# Supply_Fusing.net
KiCad netlist of a schematic drawn in Altium Designer
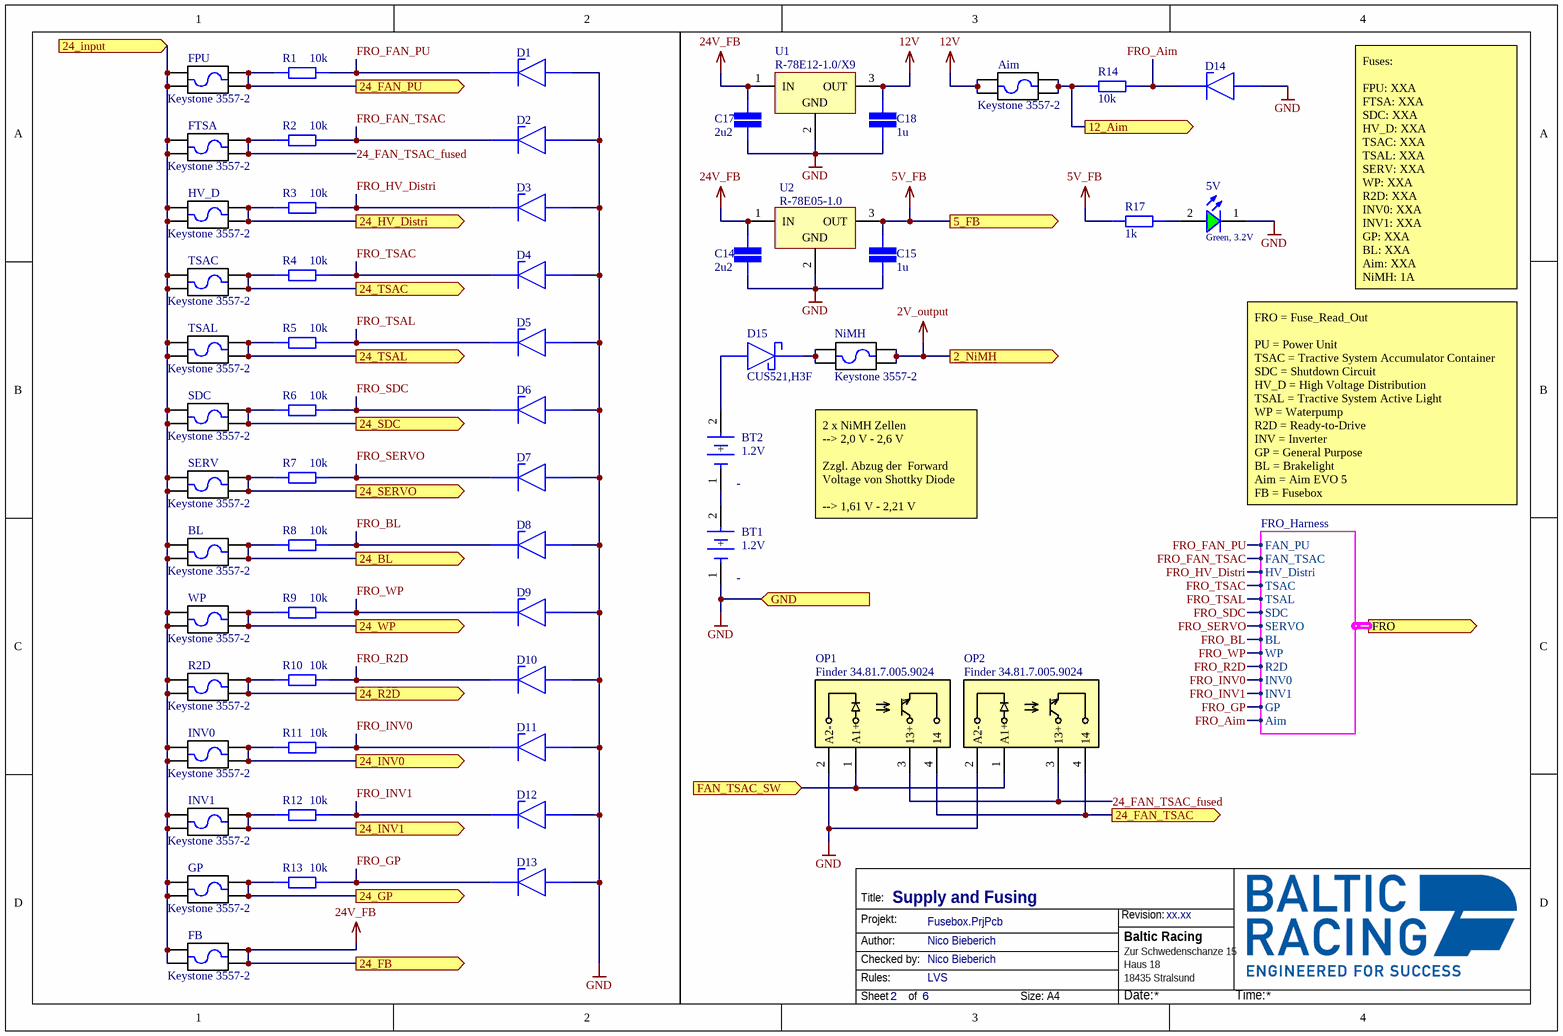
[diagram p0: Supply_Fusing.SchDoc]

(export (version "E")
  (design (tool "Eeschema 10.0.6"))
  (components
    (comp (ref "5V")
      (value "Green, 3.2V")
      (footprint "WL-SMCW_0603_H=0.7mm")
      (description "WL-SMCW SMT Mono-color Chip LED Waterclear, size 0603, Green, 3.2V, 140deg")
      (fields (field (name "PART NUMBER") "150060GS75000") (field (name "PUBLISHER") "Wurth Elektronik"))
      (libsource (lib "Altium_WL-SMCW (rev20a)") (part "150060GS75000"))
    )
    (comp (ref "Aim")
      (value "Keystone 3557-2")
      (footprint "Keystone 3557-2")
      (description "Keystone 3557-2\r\nFuse Holder")
      (libsource (lib "libNico") (part "Keystone 3557-2"))
    )
    (comp (ref "BL")
      (value "Keystone 3557-2")
      (footprint "Keystone 3557-2")
      (description "Keystone 3557-2\r\nFuse Holder")
      (libsource (lib "libNico") (part "Keystone 3557-2"))
    )
    (comp (ref "BT1")
      (value "Keystone 1020")
      (footprint "Keystone_1020_0")
      (description "BATT HOLDER BATTERY AAA SMD")
      (fields
        (field (name "PART NUMBER") "1020")
        (field (name "MANUFACTURER") "Keystone")
        (field (name "VOLTAGE") "1.2V")
      )
      (libsource (lib "libNico") (part "Keystone 1020"))
    )
    (comp (ref "BT2")
      (value "Keystone 1020")
      (footprint "Keystone_1020_0")
      (description "BATT HOLDER BATTERY AAA SMD")
      (fields
        (field (name "PART NUMBER") "1020")
        (field (name "MANUFACTURER") "Keystone")
        (field (name "VOLTAGE") "1.2V")
      )
      (libsource (lib "libNico") (part "Keystone 1020"))
    )
    (comp (ref "C14")
      (value "2u2")
      (footprint "CAP 0603/1608")
      (description "Capacitor with multiple Footprints")
      (fields (field (name "VOLTAGE") "50") (field (name "Comment") "SMD Capacitor"))
      (libsource (lib "Standardbauteile") (part "SMD Capacitor"))
    )
    (comp (ref "C15")
      (value "1u")
      (footprint "CAP 0603/1608")
      (description "Capacitor with multiple Footprints")
      (fields (field (name "VOLTAGE") "16") (field (name "Comment") "SMD Capacitor"))
      (libsource (lib "Standardbauteile") (part "SMD Capacitor"))
    )
    (comp (ref "C17")
      (value "2u2")
      (footprint "CAP 0603/1608")
      (description "Capacitor with multiple Footprints")
      (fields (field (name "VOLTAGE") "50") (field (name "Comment") "SMD Capacitor"))
      (libsource (lib "Standardbauteile") (part "SMD Capacitor"))
    )
    (comp (ref "C18")
      (value "1u")
      (footprint "CAP 0603/1608")
      (description "Capacitor with multiple Footprints")
      (fields (field (name "VOLTAGE") "16") (field (name "Comment") "SMD Capacitor"))
      (libsource (lib "Standardbauteile") (part "SMD Capacitor"))
    )
    (comp (ref "D1")
      (value "MM3Z4V7T1G")
      (footprint "SOD-323-2")
      (description "onsemi MM3Z4V7T1G\r\nZ-Diode, 4,7V")
      (libsource (lib "libNico") (part "MM3Z4V7T1G"))
    )
    (comp (ref "D2")
      (value "MM3Z4V7T1G")
      (footprint "SOD-323-2")
      (description "onsemi MM3Z4V7T1G\r\nZ-Diode, 4,7V")
      (libsource (lib "libNico") (part "MM3Z4V7T1G"))
    )
    (comp (ref "D3")
      (value "MM3Z4V7T1G")
      (footprint "SOD-323-2")
      (description "onsemi MM3Z4V7T1G\r\nZ-Diode, 4,7V")
      (libsource (lib "libNico") (part "MM3Z4V7T1G"))
    )
    (comp (ref "D4")
      (value "MM3Z4V7T1G")
      (footprint "SOD-323-2")
      (description "onsemi MM3Z4V7T1G\r\nZ-Diode, 4,7V")
      (libsource (lib "libNico") (part "MM3Z4V7T1G"))
    )
    (comp (ref "D5")
      (value "MM3Z4V7T1G")
      (footprint "SOD-323-2")
      (description "onsemi MM3Z4V7T1G\r\nZ-Diode, 4,7V")
      (libsource (lib "libNico") (part "MM3Z4V7T1G"))
    )
    (comp (ref "D6")
      (value "MM3Z4V7T1G")
      (footprint "SOD-323-2")
      (description "onsemi MM3Z4V7T1G\r\nZ-Diode, 4,7V")
      (libsource (lib "libNico") (part "MM3Z4V7T1G"))
    )
    (comp (ref "D7")
      (value "MM3Z4V7T1G")
      (footprint "SOD-323-2")
      (description "onsemi MM3Z4V7T1G\r\nZ-Diode, 4,7V")
      (libsource (lib "libNico") (part "MM3Z4V7T1G"))
    )
    (comp (ref "D8")
      (value "MM3Z4V7T1G")
      (footprint "SOD-323-2")
      (description "onsemi MM3Z4V7T1G\r\nZ-Diode, 4,7V")
      (libsource (lib "libNico") (part "MM3Z4V7T1G"))
    )
    (comp (ref "D9")
      (value "MM3Z4V7T1G")
      (footprint "SOD-323-2")
      (description "onsemi MM3Z4V7T1G\r\nZ-Diode, 4,7V")
      (libsource (lib "libNico") (part "MM3Z4V7T1G"))
    )
    (comp (ref "D10")
      (value "MM3Z4V7T1G")
      (footprint "SOD-323-2")
      (description "onsemi MM3Z4V7T1G\r\nZ-Diode, 4,7V")
      (libsource (lib "libNico") (part "MM3Z4V7T1G"))
    )
    (comp (ref "D11")
      (value "MM3Z4V7T1G")
      (footprint "SOD-323-2")
      (description "onsemi MM3Z4V7T1G\r\nZ-Diode, 4,7V")
      (libsource (lib "libNico") (part "MM3Z4V7T1G"))
    )
    (comp (ref "D12")
      (value "MM3Z4V7T1G")
      (footprint "SOD-323-2")
      (description "onsemi MM3Z4V7T1G\r\nZ-Diode, 4,7V")
      (libsource (lib "libNico") (part "MM3Z4V7T1G"))
    )
    (comp (ref "D13")
      (value "MM3Z4V7T1G")
      (footprint "SOD-323-2")
      (description "onsemi MM3Z4V7T1G\r\nZ-Diode, 4,7V")
      (libsource (lib "libNico") (part "MM3Z4V7T1G"))
    )
    (comp (ref "D14")
      (value "MM3Z4V7T1G")
      (footprint "SOD-323-2")
      (description "onsemi MM3Z4V7T1G\r\nZ-Diode, 4,7V")
      (libsource (lib "libNico") (part "MM3Z4V7T1G"))
    )
    (comp (ref "D15")
      (value "CUS521,H3F")
      (footprint "SOD-323-2")
      (description "Toshiba CUS521,H3F\r\nShottky-Diode\r\nForward: 390mV, Reverse: 30V")
      (libsource (lib "libNico") (part "CUS521,H3F"))
    )
    (comp (ref "FB")
      (value "Keystone 3557-2")
      (footprint "Keystone 3557-2")
      (description "Keystone 3557-2\r\nFuse Holder")
      (libsource (lib "libNico") (part "Keystone 3557-2"))
    )
    (comp (ref "FPU")
      (value "Keystone 3557-2")
      (footprint "Keystone 3557-2")
      (description "Keystone 3557-2\r\nFuse Holder")
      (libsource (lib "libNico") (part "Keystone 3557-2"))
    )
    (comp (ref "FTSA")
      (value "Keystone 3557-2")
      (footprint "Keystone 3557-2")
      (description "Keystone 3557-2\r\nFuse Holder")
      (libsource (lib "libNico") (part "Keystone 3557-2"))
    )
    (comp (ref "GP")
      (value "Keystone 3557-2")
      (footprint "Keystone 3557-2")
      (description "Keystone 3557-2\r\nFuse Holder")
      (libsource (lib "libNico") (part "Keystone 3557-2"))
    )
    (comp (ref "HV_D")
      (value "Keystone 3557-2")
      (footprint "Keystone 3557-2")
      (description "Keystone 3557-2\r\nFuse Holder")
      (libsource (lib "libNico") (part "Keystone 3557-2"))
    )
    (comp (ref "INV0")
      (value "Keystone 3557-2")
      (footprint "Keystone 3557-2")
      (description "Keystone 3557-2\r\nFuse Holder")
      (libsource (lib "libNico") (part "Keystone 3557-2"))
    )
    (comp (ref "INV1")
      (value "Keystone 3557-2")
      (footprint "Keystone 3557-2")
      (description "Keystone 3557-2\r\nFuse Holder")
      (libsource (lib "libNico") (part "Keystone 3557-2"))
    )
    (comp (ref "NiMH")
      (value "Keystone 3557-2")
      (footprint "Keystone 3557-2")
      (description "Keystone 3557-2\r\nFuse Holder")
      (libsource (lib "libNico") (part "Keystone 3557-2"))
    )
    (comp (ref "OP1")
      (value "Finder 34.81.7.005.9024")
      (footprint "Finder 34.81 Series")
      (description "Opto-Isolator\r\nFinder 34.81 series")
      (libsource (lib "libNico") (part "Finder 34.81 Series"))
    )
    (comp (ref "OP2")
      (value "Finder 34.81.7.005.9024")
      (footprint "Finder 34.81 Series")
      (description "Opto-Isolator\r\nFinder 34.81 series")
      (libsource (lib "libNico") (part "Finder 34.81 Series"))
    )
    (comp (ref "R1")
      (value "10k")
      (footprint "STACKPOLE CSR0603")
      (description "Resistor with multiple footprints")
      (fields (field (name "POWER") "0.1W") (field (name "Comment") "SMD Resistor"))
      (libsource (lib "Standardbauteile") (part "SMD Resistor"))
    )
    (comp (ref "R2")
      (value "10k")
      (footprint "STACKPOLE CSR0603")
      (description "Resistor with multiple footprints")
      (fields (field (name "POWER") "0.1W") (field (name "Comment") "SMD Resistor"))
      (libsource (lib "Standardbauteile") (part "SMD Resistor"))
    )
    (comp (ref "R2D")
      (value "Keystone 3557-2")
      (footprint "Keystone 3557-2")
      (description "Keystone 3557-2\r\nFuse Holder")
      (libsource (lib "libNico") (part "Keystone 3557-2"))
    )
    (comp (ref "R3")
      (value "10k")
      (footprint "STACKPOLE CSR0603")
      (description "Resistor with multiple footprints")
      (fields (field (name "POWER") "0.1W") (field (name "Comment") "SMD Resistor"))
      (libsource (lib "Standardbauteile") (part "SMD Resistor"))
    )
    (comp (ref "R4")
      (value "10k")
      (footprint "STACKPOLE CSR0603")
      (description "Resistor with multiple footprints")
      (fields (field (name "POWER") "0.1W") (field (name "Comment") "SMD Resistor"))
      (libsource (lib "Standardbauteile") (part "SMD Resistor"))
    )
    (comp (ref "R5")
      (value "10k")
      (footprint "STACKPOLE CSR0603")
      (description "Resistor with multiple footprints")
      (fields (field (name "POWER") "0.1W") (field (name "Comment") "SMD Resistor"))
      (libsource (lib "Standardbauteile") (part "SMD Resistor"))
    )
    (comp (ref "R6")
      (value "10k")
      (footprint "STACKPOLE CSR0603")
      (description "Resistor with multiple footprints")
      (fields (field (name "POWER") "0.1W") (field (name "Comment") "SMD Resistor"))
      (libsource (lib "Standardbauteile") (part "SMD Resistor"))
    )
    (comp (ref "R7")
      (value "10k")
      (footprint "STACKPOLE CSR0603")
      (description "Resistor with multiple footprints")
      (fields (field (name "POWER") "0.1W") (field (name "Comment") "SMD Resistor"))
      (libsource (lib "Standardbauteile") (part "SMD Resistor"))
    )
    (comp (ref "R8")
      (value "10k")
      (footprint "STACKPOLE CSR0603")
      (description "Resistor with multiple footprints")
      (fields (field (name "POWER") "0.1W") (field (name "Comment") "SMD Resistor"))
      (libsource (lib "Standardbauteile") (part "SMD Resistor"))
    )
    (comp (ref "R9")
      (value "10k")
      (footprint "STACKPOLE CSR0603")
      (description "Resistor with multiple footprints")
      (fields (field (name "POWER") "0.1W") (field (name "Comment") "SMD Resistor"))
      (libsource (lib "Standardbauteile") (part "SMD Resistor"))
    )
    (comp (ref "R10")
      (value "10k")
      (footprint "STACKPOLE CSR0603")
      (description "Resistor with multiple footprints")
      (fields (field (name "POWER") "0.1W") (field (name "Comment") "SMD Resistor"))
      (libsource (lib "Standardbauteile") (part "SMD Resistor"))
    )
    (comp (ref "R11")
      (value "10k")
      (footprint "STACKPOLE CSR0603")
      (description "Resistor with multiple footprints")
      (fields (field (name "POWER") "0.1W") (field (name "Comment") "SMD Resistor"))
      (libsource (lib "Standardbauteile") (part "SMD Resistor"))
    )
    (comp (ref "R12")
      (value "10k")
      (footprint "STACKPOLE CSR0603")
      (description "Resistor with multiple footprints")
      (fields (field (name "POWER") "0.1W") (field (name "Comment") "SMD Resistor"))
      (libsource (lib "Standardbauteile") (part "SMD Resistor"))
    )
    (comp (ref "R13")
      (value "10k")
      (footprint "STACKPOLE CSR0603")
      (description "Resistor with multiple footprints")
      (fields (field (name "POWER") "0.1W") (field (name "Comment") "SMD Resistor"))
      (libsource (lib "Standardbauteile") (part "SMD Resistor"))
    )
    (comp (ref "R14")
      (value "10k")
      (footprint "STACKPOLE CSR0603")
      (description "Resistor with multiple footprints")
      (fields (field (name "POWER") "0.1W") (field (name "Comment") "SMD Resistor"))
      (libsource (lib "Standardbauteile") (part "SMD Resistor"))
    )
    (comp (ref "R17")
      (value "1k")
      (footprint "STACKPOLE CSR0603")
      (description "Resistor with multiple footprints")
      (fields (field (name "POWER") "0.1W") (field (name "Comment") "SMD Resistor"))
      (libsource (lib "Standardbauteile") (part "SMD Resistor"))
    )
    (comp (ref "SDC")
      (value "Keystone 3557-2")
      (footprint "Keystone 3557-2")
      (description "Keystone 3557-2\r\nFuse Holder")
      (libsource (lib "libNico") (part "Keystone 3557-2"))
    )
    (comp (ref "SERV")
      (value "Keystone 3557-2")
      (footprint "Keystone 3557-2")
      (description "Keystone 3557-2\r\nFuse Holder")
      (libsource (lib "libNico") (part "Keystone 3557-2"))
    )
    (comp (ref "TSAC")
      (value "Keystone 3557-2")
      (footprint "Keystone 3557-2")
      (description "Keystone 3557-2\r\nFuse Holder")
      (libsource (lib "libNico") (part "Keystone 3557-2"))
    )
    (comp (ref "TSAL")
      (value "Keystone 3557-2")
      (footprint "Keystone 3557-2")
      (description "Keystone 3557-2\r\nFuse Holder")
      (libsource (lib "libNico") (part "Keystone 3557-2"))
    )
    (comp (ref "U1")
      (value "R-78E12-1.0/X9")
      (footprint "SIP3_RECOM")
      (description "Nonisolated 5V Switchmode converter")
      (libsource (lib "Standardbauteile") (part "R-78E05-1.0"))
    )
    (comp (ref "U2")
      (value "R-78E05-1.0")
      (footprint "SIP3_RECOM")
      (description "Nonisolated 5V Switchmode converter")
      (libsource (lib "Standardbauteile") (part "R-78E05-1.0"))
    )
    (comp (ref "WP")
      (value "Keystone 3557-2")
      (footprint "Keystone 3557-2")
      (description "Keystone 3557-2\r\nFuse Holder")
      (libsource (lib "libNico") (part "Keystone 3557-2"))
    )
  )
  (nets
    (net (code "2") (name "/12_Aim") (class "Default")
      (node (ref "Aim") (pin "O1") (pinfunction "O1_O1") (pintype "passive"))
      (node (ref "Aim") (pin "O2") (pinfunction "O2_O2") (pintype "passive"))
      (node (ref "R14") (pin "2") (pinfunction "2_2") (pintype "passive"))
    )
    (net (code "3") (name "/24_BL") (class "Default")
      (node (ref "BL") (pin "O1") (pinfunction "O1_O1") (pintype "passive"))
      (node (ref "BL") (pin "O2") (pinfunction "O2_O2") (pintype "passive"))
      (node (ref "R8") (pin "2") (pinfunction "2_2") (pintype "passive"))
    )
    (net (code "4") (name "/24_FAN_PU") (class "Default")
      (node (ref "FPU") (pin "O1") (pinfunction "O1_O1") (pintype "passive"))
      (node (ref "FPU") (pin "O2") (pinfunction "O2_O2") (pintype "passive"))
      (node (ref "R1") (pin "2") (pinfunction "2_2") (pintype "passive"))
    )
    (net (code "5") (name "/24_FAN_TSAC") (class "Default")
      (node (ref "OP1") (pin "4") (pinfunction "14_4") (pintype "passive"))
      (node (ref "OP2") (pin "4") (pinfunction "14_4") (pintype "passive"))
    )
    (net (code "6") (name "/24_FAN_TSAC_fused") (class "Default")
      (node (ref "FTSA") (pin "O1") (pinfunction "O1_O1") (pintype "passive"))
      (node (ref "FTSA") (pin "O2") (pinfunction "O2_O2") (pintype "passive"))
      (node (ref "OP1") (pin "3") (pinfunction "13+_3") (pintype "passive"))
      (node (ref "OP2") (pin "3") (pinfunction "13+_3") (pintype "passive"))
      (node (ref "R2") (pin "2") (pinfunction "2_2") (pintype "passive"))
    )
    (net (code "7") (name "/24_GP") (class "Default")
      (node (ref "GP") (pin "O1") (pinfunction "O1_O1") (pintype "passive"))
      (node (ref "GP") (pin "O2") (pinfunction "O2_O2") (pintype "passive"))
      (node (ref "R13") (pin "2") (pinfunction "2_2") (pintype "passive"))
    )
    (net (code "8") (name "/24_HV_Distri") (class "Default")
      (node (ref "HV_D") (pin "O1") (pinfunction "O1_O1") (pintype "passive"))
      (node (ref "HV_D") (pin "O2") (pinfunction "O2_O2") (pintype "passive"))
      (node (ref "R3") (pin "2") (pinfunction "2_2") (pintype "passive"))
    )
    (net (code "9") (name "/24_INV0") (class "Default")
      (node (ref "INV0") (pin "O1") (pinfunction "O1_O1") (pintype "passive"))
      (node (ref "INV0") (pin "O2") (pinfunction "O2_O2") (pintype "passive"))
      (node (ref "R11") (pin "2") (pinfunction "2_2") (pintype "passive"))
    )
    (net (code "10") (name "/24_INV1") (class "Default")
      (node (ref "INV1") (pin "O1") (pinfunction "O1_O1") (pintype "passive"))
      (node (ref "INV1") (pin "O2") (pinfunction "O2_O2") (pintype "passive"))
      (node (ref "R12") (pin "2") (pinfunction "2_2") (pintype "passive"))
    )
    (net (code "11") (name "/24_R2D") (class "Default")
      (node (ref "R10") (pin "2") (pinfunction "2_2") (pintype "passive"))
      (node (ref "R2D") (pin "O1") (pinfunction "O1_O1") (pintype "passive"))
      (node (ref "R2D") (pin "O2") (pinfunction "O2_O2") (pintype "passive"))
    )
    (net (code "12") (name "/24_SDC") (class "Default")
      (node (ref "R6") (pin "2") (pinfunction "2_2") (pintype "passive"))
      (node (ref "SDC") (pin "O1") (pinfunction "O1_O1") (pintype "passive"))
      (node (ref "SDC") (pin "O2") (pinfunction "O2_O2") (pintype "passive"))
    )
    (net (code "13") (name "/24_SERVO") (class "Default")
      (node (ref "R7") (pin "2") (pinfunction "2_2") (pintype "passive"))
      (node (ref "SERV") (pin "O1") (pinfunction "O1_O1") (pintype "passive"))
      (node (ref "SERV") (pin "O2") (pinfunction "O2_O2") (pintype "passive"))
    )
    (net (code "14") (name "/24_TSAC") (class "Default")
      (node (ref "R4") (pin "2") (pinfunction "2_2") (pintype "passive"))
      (node (ref "TSAC") (pin "O1") (pinfunction "O1_O1") (pintype "passive"))
      (node (ref "TSAC") (pin "O2") (pinfunction "O2_O2") (pintype "passive"))
    )
    (net (code "15") (name "/24_TSAL") (class "Default")
      (node (ref "R5") (pin "2") (pinfunction "2_2") (pintype "passive"))
      (node (ref "TSAL") (pin "O1") (pinfunction "O1_O1") (pintype "passive"))
      (node (ref "TSAL") (pin "O2") (pinfunction "O2_O2") (pintype "passive"))
    )
    (net (code "16") (name "/24_WP") (class "Default")
      (node (ref "R9") (pin "2") (pinfunction "2_2") (pintype "passive"))
      (node (ref "WP") (pin "O1") (pinfunction "O1_O1") (pintype "passive"))
      (node (ref "WP") (pin "O2") (pinfunction "O2_O2") (pintype "passive"))
    )
    (net (code "17") (name "/24_input") (class "Default")
      (node (ref "BL") (pin "I1") (pinfunction "I1_I1") (pintype "passive"))
      (node (ref "BL") (pin "I2") (pinfunction "I2_I2") (pintype "passive"))
      (node (ref "FB") (pin "I1") (pinfunction "I1_I1") (pintype "passive"))
      (node (ref "FB") (pin "I2") (pinfunction "I2_I2") (pintype "passive"))
      (node (ref "FPU") (pin "I1") (pinfunction "I1_I1") (pintype "passive"))
      (node (ref "FPU") (pin "I2") (pinfunction "I2_I2") (pintype "passive"))
      (node (ref "FTSA") (pin "I1") (pinfunction "I1_I1") (pintype "passive"))
      (node (ref "FTSA") (pin "I2") (pinfunction "I2_I2") (pintype "passive"))
      (node (ref "GP") (pin "I1") (pinfunction "I1_I1") (pintype "passive"))
      (node (ref "GP") (pin "I2") (pinfunction "I2_I2") (pintype "passive"))
      (node (ref "HV_D") (pin "I1") (pinfunction "I1_I1") (pintype "passive"))
      (node (ref "HV_D") (pin "I2") (pinfunction "I2_I2") (pintype "passive"))
      (node (ref "INV0") (pin "I1") (pinfunction "I1_I1") (pintype "passive"))
      (node (ref "INV0") (pin "I2") (pinfunction "I2_I2") (pintype "passive"))
      (node (ref "INV1") (pin "I1") (pinfunction "I1_I1") (pintype "passive"))
      (node (ref "INV1") (pin "I2") (pinfunction "I2_I2") (pintype "passive"))
      (node (ref "R2D") (pin "I1") (pinfunction "I1_I1") (pintype "passive"))
      (node (ref "R2D") (pin "I2") (pinfunction "I2_I2") (pintype "passive"))
      (node (ref "SDC") (pin "I1") (pinfunction "I1_I1") (pintype "passive"))
      (node (ref "SDC") (pin "I2") (pinfunction "I2_I2") (pintype "passive"))
      (node (ref "SERV") (pin "I1") (pinfunction "I1_I1") (pintype "passive"))
      (node (ref "SERV") (pin "I2") (pinfunction "I2_I2") (pintype "passive"))
      (node (ref "TSAC") (pin "I1") (pinfunction "I1_I1") (pintype "passive"))
      (node (ref "TSAC") (pin "I2") (pinfunction "I2_I2") (pintype "passive"))
      (node (ref "TSAL") (pin "I1") (pinfunction "I1_I1") (pintype "passive"))
      (node (ref "TSAL") (pin "I2") (pinfunction "I2_I2") (pintype "passive"))
      (node (ref "WP") (pin "I1") (pinfunction "I1_I1") (pintype "passive"))
      (node (ref "WP") (pin "I2") (pinfunction "I2_I2") (pintype "passive"))
    )
    (net (code "18") (name "/FAN_TSAC_SW") (class "Default")
      (node (ref "OP1") (pin "1") (pinfunction "A1+_1") (pintype "passive"))
      (node (ref "OP2") (pin "1") (pinfunction "A1+_1") (pintype "passive"))
    )
    (net (code "19") (name "/FRO_Aim") (class "Default")
      (node (ref "D14") (pin "1C") (pinfunction "C_1C") (pintype "passive"))
      (node (ref "R14") (pin "1") (pinfunction "1_1") (pintype "passive"))
    )
    (net (code "20") (name "/FRO_BL") (class "Default")
      (node (ref "D8") (pin "1C") (pinfunction "C_1C") (pintype "passive"))
      (node (ref "R8") (pin "1") (pinfunction "1_1") (pintype "passive"))
    )
    (net (code "21") (name "/FRO_FAN_PU") (class "Default")
      (node (ref "D1") (pin "1C") (pinfunction "C_1C") (pintype "passive"))
      (node (ref "R1") (pin "1") (pinfunction "1_1") (pintype "passive"))
    )
    (net (code "22") (name "/FRO_FAN_TSAC") (class "Default")
      (node (ref "D2") (pin "1C") (pinfunction "C_1C") (pintype "passive"))
      (node (ref "R2") (pin "1") (pinfunction "1_1") (pintype "passive"))
    )
    (net (code "23") (name "/FRO_GP") (class "Default")
      (node (ref "D13") (pin "1C") (pinfunction "C_1C") (pintype "passive"))
      (node (ref "R13") (pin "1") (pinfunction "1_1") (pintype "passive"))
    )
    (net (code "24") (name "/FRO_HV_Distri") (class "Default")
      (node (ref "D3") (pin "1C") (pinfunction "C_1C") (pintype "passive"))
      (node (ref "R3") (pin "1") (pinfunction "1_1") (pintype "passive"))
    )
    (net (code "25") (name "/FRO_INV0") (class "Default")
      (node (ref "D11") (pin "1C") (pinfunction "C_1C") (pintype "passive"))
      (node (ref "R11") (pin "1") (pinfunction "1_1") (pintype "passive"))
    )
    (net (code "26") (name "/FRO_INV1") (class "Default")
      (node (ref "D12") (pin "1C") (pinfunction "C_1C") (pintype "passive"))
      (node (ref "R12") (pin "1") (pinfunction "1_1") (pintype "passive"))
    )
    (net (code "27") (name "/FRO_R2D") (class "Default")
      (node (ref "D10") (pin "1C") (pinfunction "C_1C") (pintype "passive"))
      (node (ref "R10") (pin "1") (pinfunction "1_1") (pintype "passive"))
    )
    (net (code "28") (name "/FRO_SDC") (class "Default")
      (node (ref "D6") (pin "1C") (pinfunction "C_1C") (pintype "passive"))
      (node (ref "R6") (pin "1") (pinfunction "1_1") (pintype "passive"))
    )
    (net (code "29") (name "/FRO_SERVO") (class "Default")
      (node (ref "D7") (pin "1C") (pinfunction "C_1C") (pintype "passive"))
      (node (ref "R7") (pin "1") (pinfunction "1_1") (pintype "passive"))
    )
    (net (code "30") (name "/FRO_TSAC") (class "Default")
      (node (ref "D4") (pin "1C") (pinfunction "C_1C") (pintype "passive"))
      (node (ref "R4") (pin "1") (pinfunction "1_1") (pintype "passive"))
    )
    (net (code "31") (name "/FRO_TSAL") (class "Default")
      (node (ref "D5") (pin "1C") (pinfunction "C_1C") (pintype "passive"))
      (node (ref "R5") (pin "1") (pinfunction "1_1") (pintype "passive"))
    )
    (net (code "32") (name "/FRO_WP") (class "Default")
      (node (ref "D9") (pin "1C") (pinfunction "C_1C") (pintype "passive"))
      (node (ref "R9") (pin "1") (pinfunction "1_1") (pintype "passive"))
    )
    (net (code "34") (name "2V_output") (class "Default")
      (node (ref "NiMH") (pin "O1") (pinfunction "O1_O1") (pintype "passive"))
      (node (ref "NiMH") (pin "O2") (pinfunction "O2_O2") (pintype "passive"))
    )
    (net (code "35") (name "5V_FB") (class "Default")
      (node (ref "C15") (pin "2") (pinfunction "2_2") (pintype "passive"))
      (node (ref "R17") (pin "2") (pinfunction "2_2") (pintype "passive"))
      (node (ref "U2") (pin "3") (pinfunction "OUT_3") (pintype "power_in"))
    )
    (net (code "36") (name "12V") (class "Default")
      (node (ref "Aim") (pin "I1") (pinfunction "I1_I1") (pintype "passive"))
      (node (ref "Aim") (pin "I2") (pinfunction "I2_I2") (pintype "passive"))
      (node (ref "C18") (pin "2") (pinfunction "2_2") (pintype "passive"))
      (node (ref "U1") (pin "3") (pinfunction "OUT_3") (pintype "power_in"))
    )
    (net (code "37") (name "24V_FB") (class "Default")
      (node (ref "C14") (pin "2") (pinfunction "2_2") (pintype "passive"))
      (node (ref "C17") (pin "2") (pinfunction "2_2") (pintype "passive"))
      (node (ref "FB") (pin "O1") (pinfunction "O1_O1") (pintype "passive"))
      (node (ref "FB") (pin "O2") (pinfunction "O2_O2") (pintype "passive"))
      (node (ref "U1") (pin "1") (pinfunction "IN_1") (pintype "power_in"))
      (node (ref "U2") (pin "1") (pinfunction "IN_1") (pintype "power_in"))
    )
    (net (code "38") (name "GND") (class "Default")
      (node (ref "5V") (pin "1") (pinfunction "K_1") (pintype "passive"))
      (node (ref "BT1") (pin "1") (pinfunction "-_1") (pintype "passive"))
      (node (ref "C14") (pin "1") (pinfunction "1_1") (pintype "passive"))
      (node (ref "C15") (pin "1") (pinfunction "1_1") (pintype "passive"))
      (node (ref "C17") (pin "1") (pinfunction "1_1") (pintype "passive"))
      (node (ref "C18") (pin "1") (pinfunction "1_1") (pintype "passive"))
      (node (ref "D1") (pin "2A") (pinfunction "A_2A") (pintype "passive"))
      (node (ref "D10") (pin "2A") (pinfunction "A_2A") (pintype "passive"))
      (node (ref "D11") (pin "2A") (pinfunction "A_2A") (pintype "passive"))
      (node (ref "D12") (pin "2A") (pinfunction "A_2A") (pintype "passive"))
      (node (ref "D13") (pin "2A") (pinfunction "A_2A") (pintype "passive"))
      (node (ref "D14") (pin "2A") (pinfunction "A_2A") (pintype "passive"))
      (node (ref "D2") (pin "2A") (pinfunction "A_2A") (pintype "passive"))
      (node (ref "D3") (pin "2A") (pinfunction "A_2A") (pintype "passive"))
      (node (ref "D4") (pin "2A") (pinfunction "A_2A") (pintype "passive"))
      (node (ref "D5") (pin "2A") (pinfunction "A_2A") (pintype "passive"))
      (node (ref "D6") (pin "2A") (pinfunction "A_2A") (pintype "passive"))
      (node (ref "D7") (pin "2A") (pinfunction "A_2A") (pintype "passive"))
      (node (ref "D8") (pin "2A") (pinfunction "A_2A") (pintype "passive"))
      (node (ref "D9") (pin "2A") (pinfunction "A_2A") (pintype "passive"))
      (node (ref "OP1") (pin "2") (pinfunction "A2-_2") (pintype "passive"))
      (node (ref "OP2") (pin "2") (pinfunction "A2-_2") (pintype "passive"))
      (node (ref "U1") (pin "2") (pinfunction "GND_2") (pintype "power_in"))
      (node (ref "U2") (pin "2") (pinfunction "GND_2") (pintype "power_in"))
    )
    (net (code "39") (name "Net-(5V-A)") (class "Default")
      (node (ref "5V") (pin "2") (pinfunction "A_2") (pintype "passive"))
      (node (ref "R17") (pin "1") (pinfunction "1_1") (pintype "passive"))
    )
    (net (code "40") (name "Net-(BT1-+)") (class "Default")
      (node (ref "BT1") (pin "2") (pinfunction "+_2") (pintype "passive"))
      (node (ref "BT2") (pin "1") (pinfunction "-_1") (pintype "passive"))
    )
    (net (code "41") (name "Net-(BT2-+)") (class "Default")
      (node (ref "BT2") (pin "2") (pinfunction "+_2") (pintype "passive"))
      (node (ref "D15") (pin "2A") (pinfunction "A_2A") (pintype "passive"))
    )
    (net (code "42") (name "Net-(D15-C)") (class "Default")
      (node (ref "D15") (pin "1C") (pinfunction "C_1C") (pintype "passive"))
      (node (ref "NiMH") (pin "I1") (pinfunction "I1_I1") (pintype "passive"))
      (node (ref "NiMH") (pin "I2") (pinfunction "I2_I2") (pintype "passive"))
    )
  )
)
